# kr3.net
KiCad netlist of a schematic drawn in Altium Designer
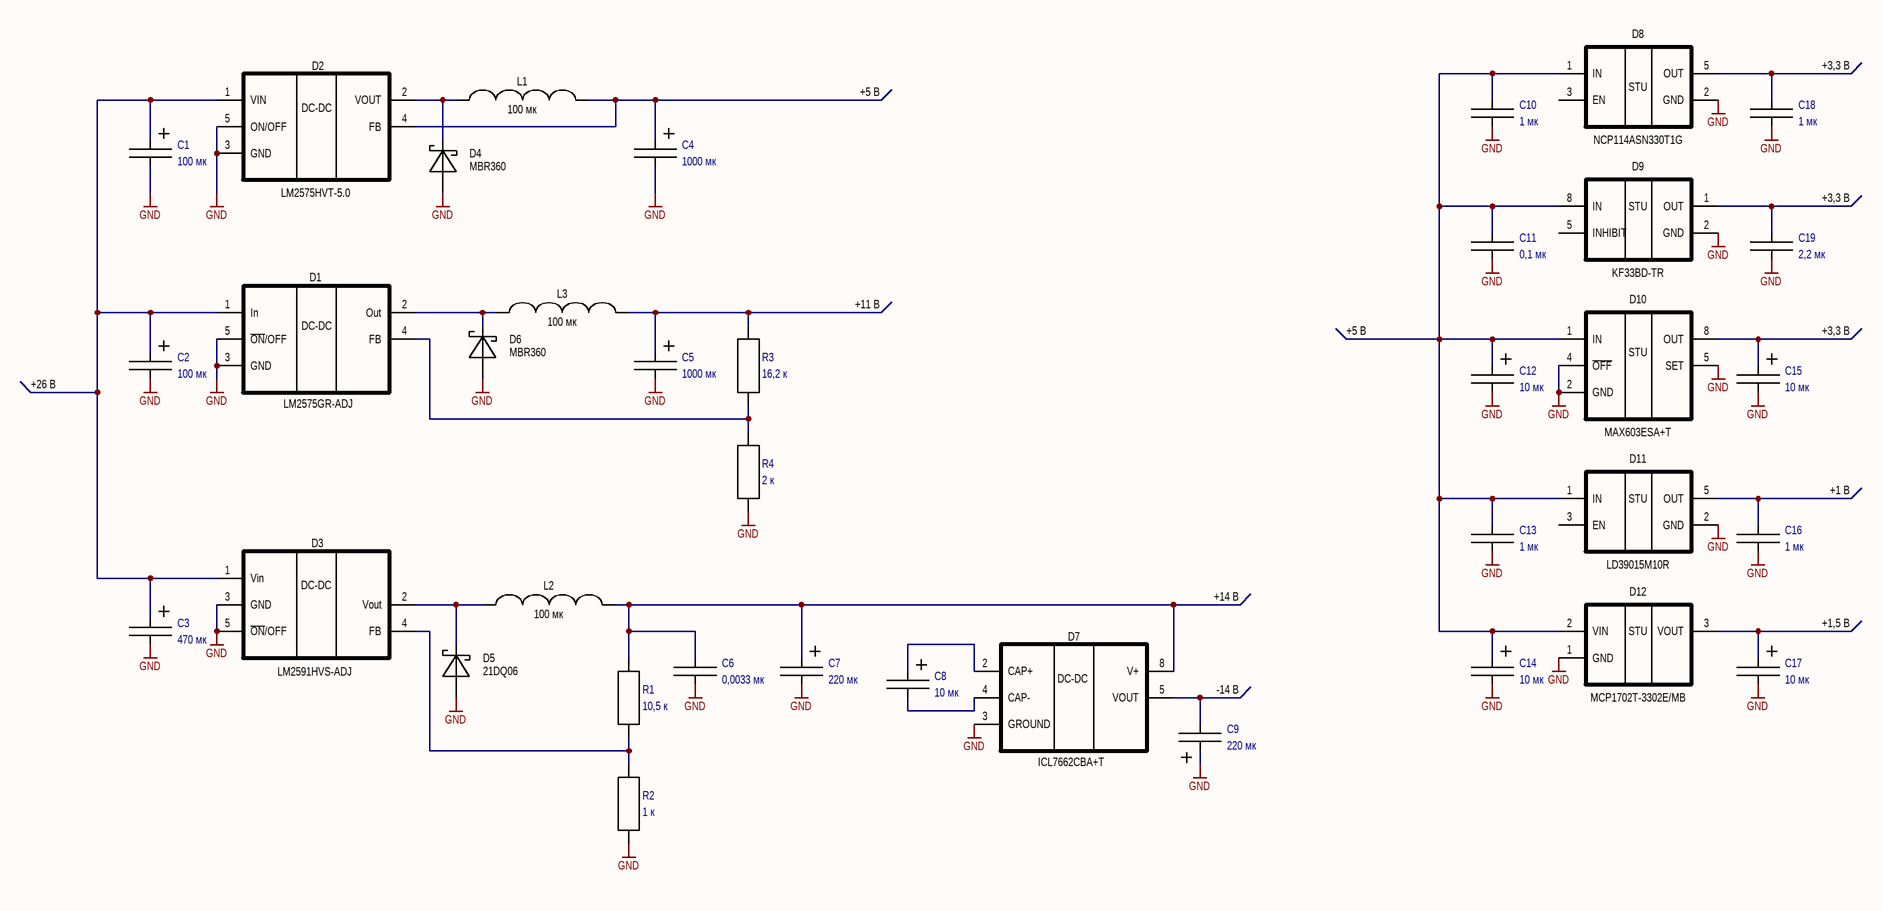
[diagram p0: kr3.SchDoc]

(export (version "E")
  (design (tool "Eeschema 10.0.6"))
  (components
    (comp (ref "C1")
      (value "100 мк")
      (fields (field (name "Comment") "100 мкФ ±* * * *, *"))
      (libsource (lib "STO") (part "C+"))
    )
    (comp (ref "C2")
      (value "100 мк")
      (fields (field (name "Comment") "100 мкФ ±* * * *, *"))
      (libsource (lib "STO") (part "C+"))
    )
    (comp (ref "C3")
      (value "470 мк")
      (fields (field (name "Comment") "470 мкФ ±* * * *, *"))
      (libsource (lib "STO") (part "C+"))
    )
    (comp (ref "C4")
      (value "1000 мк")
      (fields (field (name "Comment") "1000 мкФ ±* * * *, *"))
      (libsource (lib "STO") (part "C+"))
    )
    (comp (ref "C5")
      (value "1000 мк")
      (fields (field (name "Comment") "1000 мкФ ±* * * *, *"))
      (libsource (lib "STO") (part "C+"))
    )
    (comp (ref "C6")
      (value "0,0033 мк")
      (fields (field (name "Comment") "0,0033 мкФ ±* * * *, *"))
      (libsource (lib "STO") (part "C"))
    )
    (comp (ref "C7")
      (value "220 мк")
      (fields (field (name "Comment") "220 мкФ ±* * * *, *"))
      (libsource (lib "STO") (part "C+"))
    )
    (comp (ref "C8")
      (value "10 мк")
      (fields (field (name "Comment") "10 мкФ ±* * * *, *"))
      (libsource (lib "STO") (part "C+"))
    )
    (comp (ref "C9")
      (value "220 мк")
      (fields (field (name "Comment") "220 мкФ ±* * * *, *"))
      (libsource (lib "STO") (part "C+"))
    )
    (comp (ref "C10")
      (value "1 мк")
      (fields (field (name "Comment") "1 мкФ ±* * * *, *"))
      (libsource (lib "STO") (part "C"))
    )
    (comp (ref "C11")
      (value "0,1 мк")
      (fields (field (name "Comment") "0,1 мкФ ±* * * *, *"))
      (libsource (lib "STO") (part "C"))
    )
    (comp (ref "C12")
      (value "10 мк")
      (fields (field (name "Comment") "10 мкФ ±* * * *, *"))
      (libsource (lib "STO") (part "C+"))
    )
    (comp (ref "C13")
      (value "1 мк")
      (fields (field (name "Comment") "1 мкФ ±* * * *, *"))
      (libsource (lib "STO") (part "C"))
    )
    (comp (ref "C14")
      (value "10 мк")
      (fields (field (name "Comment") "10 мкФ ±* * * *, *"))
      (libsource (lib "STO") (part "C+"))
    )
    (comp (ref "C15")
      (value "10 мк")
      (fields (field (name "Comment") "10 мкФ ±* * * *, *"))
      (libsource (lib "STO") (part "C+"))
    )
    (comp (ref "C16")
      (value "1 мк")
      (fields (field (name "Comment") "1 мкФ ±* * * *, *"))
      (libsource (lib "STO") (part "C"))
    )
    (comp (ref "C17")
      (value "10 мк")
      (fields (field (name "Comment") "10 мкФ ±* * * *, *"))
      (libsource (lib "STO") (part "C+"))
    )
    (comp (ref "C18")
      (value "1 мк")
      (fields (field (name "Comment") "1 мкФ ±* * * *, *"))
      (libsource (lib "STO") (part "C"))
    )
    (comp (ref "C19")
      (value "2,2 мк")
      (fields (field (name "Comment") "2,2 мкФ ±* * * *, *"))
      (libsource (lib "STO") (part "C"))
    )
    (comp (ref "D1") (value "LM2575GR-ADJ") (libsource (lib "STO") (part "LM2575GR-ADJ")))
    (comp (ref "D2") (value "LM2575HVT-5.0") (libsource (lib "STO") (part "LM2575HVT-5.0")))
    (comp (ref "D3") (value "LM2591HVS-ADJ") (libsource (lib "STO") (part "LM2591HVS-ADJ")))
    (comp (ref "D4") (value "MBR360") (libsource (lib "STO") (part "MBR360")))
    (comp (ref "D5") (value "21DQ06") (libsource (lib "STO") (part "MBR360")))
    (comp (ref "D6") (value "MBR360") (libsource (lib "STO") (part "MBR360")))
    (comp (ref "D7") (value "ICL7662CBA+T") (libsource (lib "STO") (part "ICL7662CBA+T")))
    (comp (ref "D8") (value "NCP114ASN330T1G") (libsource (lib "STO") (part "NCP114ASN330T1G")))
    (comp (ref "D9") (value "KF33BD-TR") (libsource (lib "STO") (part "KF33BD-TR")))
    (comp (ref "D10") (value "MAX603ESA+T") (libsource (lib "STO") (part "MAX603ESA+T")))
    (comp (ref "D11") (value "LD39015M10R") (libsource (lib "STO") (part "LD39015M10R")))
    (comp (ref "D12") (value "MCP1702T-3302E/MB") (libsource (lib "STO") (part "MCP1702T-3302E/MB")))
    (comp (ref "L1") (value "100 мк") (libsource (lib "STO") (part "Inductor Sumida")))
    (comp (ref "L2") (value "100 мк") (libsource (lib "STO") (part "Inductor Sumida")))
    (comp (ref "L3") (value "100 мк") (libsource (lib "STO") (part "Inductor Sumida")))
    (comp (ref "R1")
      (value "10,5 к")
      (fields (field (name "Comment") "10,5 кОм ±* *, *"))
      (libsource (lib "STO") (part "R"))
    )
    (comp (ref "R2")
      (value "1 к")
      (fields (field (name "Comment") "1 кОм ±* *, *"))
      (libsource (lib "STO") (part "R"))
    )
    (comp (ref "R3")
      (value "16,2 к")
      (fields (field (name "Comment") "16,2 кОм ±* *, *"))
      (libsource (lib "STO") (part "R"))
    )
    (comp (ref "R4")
      (value "2 к")
      (fields (field (name "Comment") "2 кОм ±* *, *"))
      (libsource (lib "STO") (part "R"))
    )
  )
  (nets
    (net (code "1") (name "GND") (class "Default")
      (node (ref "C1") (pin "2") (pinfunction "2_2") (pintype "passive"))
      (node (ref "C10") (pin "2") (pinfunction "2_2") (pintype "passive"))
      (node (ref "C11") (pin "2") (pinfunction "2_2") (pintype "passive"))
      (node (ref "C12") (pin "2") (pinfunction "2_2") (pintype "passive"))
      (node (ref "C13") (pin "2") (pinfunction "2_2") (pintype "passive"))
      (node (ref "C14") (pin "2") (pinfunction "2_2") (pintype "passive"))
      (node (ref "C15") (pin "2") (pinfunction "2_2") (pintype "passive"))
      (node (ref "C16") (pin "2") (pinfunction "2_2") (pintype "passive"))
      (node (ref "C17") (pin "2") (pinfunction "2_2") (pintype "passive"))
      (node (ref "C18") (pin "2") (pinfunction "2_2") (pintype "passive"))
      (node (ref "C19") (pin "2") (pinfunction "2_2") (pintype "passive"))
      (node (ref "C2") (pin "2") (pinfunction "2_2") (pintype "passive"))
      (node (ref "C3") (pin "2") (pinfunction "2_2") (pintype "passive"))
      (node (ref "C4") (pin "2") (pinfunction "2_2") (pintype "passive"))
      (node (ref "C5") (pin "2") (pinfunction "2_2") (pintype "passive"))
      (node (ref "C6") (pin "2") (pinfunction "2_2") (pintype "passive"))
      (node (ref "C7") (pin "2") (pinfunction "2_2") (pintype "passive"))
      (node (ref "C9") (pin "1") (pinfunction "1_1") (pintype "passive"))
      (node (ref "D1") (pin "3") (pinfunction "GND_3") (pintype "passive"))
      (node (ref "D1") (pin "5") (pinfunction "~{ON}/OFF_5") (pintype "passive"))
      (node (ref "D10") (pin "2") (pinfunction "GND_2") (pintype "passive"))
      (node (ref "D10") (pin "4") (pinfunction "~{OFF}_4") (pintype "passive"))
      (node (ref "D10") (pin "5") (pinfunction "SET_5") (pintype "passive"))
      (node (ref "D11") (pin "2") (pinfunction "GND_2") (pintype "passive"))
      (node (ref "D12") (pin "1") (pinfunction "GND_1") (pintype "passive"))
      (node (ref "D2") (pin "3") (pinfunction "GND_3") (pintype "passive"))
      (node (ref "D2") (pin "5") (pinfunction "ON/OFF_5") (pintype "passive"))
      (node (ref "D3") (pin "3") (pinfunction "GND_3") (pintype "passive"))
      (node (ref "D3") (pin "5") (pinfunction "~{ON}/OFF_5") (pintype "passive"))
      (node (ref "D4") (pin "1") (pinfunction "A_1") (pintype "passive"))
      (node (ref "D5") (pin "1") (pinfunction "A_1") (pintype "passive"))
      (node (ref "D6") (pin "1") (pinfunction "A_1") (pintype "passive"))
      (node (ref "D7") (pin "3") (pinfunction "GROUND_3") (pintype "passive"))
      (node (ref "D8") (pin "2") (pinfunction "GND_2") (pintype "passive"))
      (node (ref "D9") (pin "2") (pinfunction "GND_2") (pintype "passive"))
      (node (ref "R2") (pin "2") (pinfunction "2_2") (pintype "passive"))
      (node (ref "R4") (pin "2") (pinfunction "2_2") (pintype "passive"))
    )
    (net (code "2") (name "Net-(C5-Pad1)") (class "Default")
      (node (ref "C5") (pin "1") (pinfunction "1_1") (pintype "passive"))
      (node (ref "R3") (pin "1") (pinfunction "1_1") (pintype "passive"))
    )
    (net (code "3") (name "Net-(D1-FB)") (class "Default")
      (node (ref "D1") (pin "4") (pinfunction "FB_4") (pintype "passive"))
      (node (ref "R3") (pin "2") (pinfunction "2_2") (pintype "passive"))
      (node (ref "R4") (pin "1") (pinfunction "1_1") (pintype "passive"))
    )
    (net (code "4") (name "Net-(D1-In)") (class "Default")
      (node (ref "C1") (pin "1") (pinfunction "1_1") (pintype "passive"))
      (node (ref "C2") (pin "1") (pinfunction "1_1") (pintype "passive"))
      (node (ref "C3") (pin "1") (pinfunction "1_1") (pintype "passive"))
      (node (ref "D1") (pin "1") (pinfunction "In_1") (pintype "passive"))
      (node (ref "D2") (pin "1") (pinfunction "VIN_1") (pintype "passive"))
      (node (ref "D3") (pin "1") (pinfunction "Vin_1") (pintype "passive"))
    )
    (net (code "5") (name "Net-(D1-Out)") (class "Default")
      (node (ref "D1") (pin "2") (pinfunction "Out_2") (pintype "passive"))
      (node (ref "D6") (pin "1") (pinfunction "C_1") (pintype "passive"))
    )
    (net (code "6") (name "Net-(D2-FB)") (class "Default")
      (node (ref "C4") (pin "1") (pinfunction "1_1") (pintype "passive"))
      (node (ref "D2") (pin "4") (pinfunction "FB_4") (pintype "passive"))
    )
    (net (code "7") (name "Net-(D2-VOUT)") (class "Default")
      (node (ref "D2") (pin "2") (pinfunction "VOUT_2") (pintype "passive"))
      (node (ref "D4") (pin "1") (pinfunction "C_1") (pintype "passive"))
    )
    (net (code "8") (name "Net-(D3-FB)") (class "Default")
      (node (ref "D3") (pin "4") (pinfunction "FB_4") (pintype "passive"))
      (node (ref "R1") (pin "2") (pinfunction "2_2") (pintype "passive"))
      (node (ref "R2") (pin "1") (pinfunction "1_1") (pintype "passive"))
    )
    (net (code "9") (name "Net-(D3-Vout)") (class "Default")
      (node (ref "D3") (pin "2") (pinfunction "Vout_2") (pintype "passive"))
      (node (ref "D5") (pin "1") (pinfunction "C_1") (pintype "passive"))
    )
    (net (code "10") (name "Net-(D7-CAP+)") (class "Default")
      (node (ref "C8") (pin "1") (pinfunction "1_1") (pintype "passive"))
      (node (ref "D7") (pin "2") (pinfunction "CAP+_2") (pintype "passive"))
    )
    (net (code "11") (name "Net-(D7-CAP-)") (class "Default")
      (node (ref "C8") (pin "2") (pinfunction "2_2") (pintype "passive"))
      (node (ref "D7") (pin "4") (pinfunction "CAP-_4") (pintype "passive"))
    )
    (net (code "12") (name "Net-(D7-V+)") (class "Default")
      (node (ref "C6") (pin "1") (pinfunction "1_1") (pintype "passive"))
      (node (ref "C7") (pin "1") (pinfunction "1_1") (pintype "passive"))
      (node (ref "D7") (pin "8") (pinfunction "V+_8") (pintype "passive"))
      (node (ref "R1") (pin "1") (pinfunction "1_1") (pintype "passive"))
    )
    (net (code "13") (name "Net-(D7-VOUT)") (class "Default")
      (node (ref "C9") (pin "2") (pinfunction "2_2") (pintype "passive"))
      (node (ref "D7") (pin "5") (pinfunction "VOUT_5") (pintype "passive"))
    )
    (net (code "14") (name "Net-(D8-OUT)") (class "Default")
      (node (ref "C18") (pin "1") (pinfunction "1_1") (pintype "passive"))
      (node (ref "D8") (pin "5") (pinfunction "OUT_5") (pintype "passive"))
    )
    (net (code "15") (name "Net-(D9-OUT)") (class "Default")
      (node (ref "C19") (pin "1") (pinfunction "1_1") (pintype "passive"))
      (node (ref "D9") (pin "1") (pinfunction "OUT_1") (pintype "passive"))
    )
    (net (code "16") (name "Net-(D10-IN)") (class "Default")
      (node (ref "C10") (pin "1") (pinfunction "1_1") (pintype "passive"))
      (node (ref "C11") (pin "1") (pinfunction "1_1") (pintype "passive"))
      (node (ref "C12") (pin "1") (pinfunction "1_1") (pintype "passive"))
      (node (ref "C13") (pin "1") (pinfunction "1_1") (pintype "passive"))
      (node (ref "C14") (pin "1") (pinfunction "1_1") (pintype "passive"))
      (node (ref "D10") (pin "1") (pinfunction "IN_1") (pintype "passive"))
      (node (ref "D11") (pin "1") (pinfunction "IN_1") (pintype "passive"))
      (node (ref "D12") (pin "2") (pinfunction "VIN_2") (pintype "passive"))
      (node (ref "D8") (pin "1") (pinfunction "IN_1") (pintype "passive"))
      (node (ref "D9") (pin "8") (pinfunction "IN_8") (pintype "passive"))
    )
    (net (code "17") (name "Net-(D10-OUT)") (class "Default")
      (node (ref "C15") (pin "1") (pinfunction "1_1") (pintype "passive"))
      (node (ref "D10") (pin "8") (pinfunction "OUT_8") (pintype "passive"))
    )
    (net (code "18") (name "Net-(D11-OUT)") (class "Default")
      (node (ref "C16") (pin "1") (pinfunction "1_1") (pintype "passive"))
      (node (ref "D11") (pin "5") (pinfunction "OUT_5") (pintype "passive"))
    )
    (net (code "19") (name "Net-(D12-VOUT)") (class "Default")
      (node (ref "C17") (pin "1") (pinfunction "1_1") (pintype "passive"))
      (node (ref "D12") (pin "3") (pinfunction "VOUT_3") (pintype "passive"))
    )
    (net (code "20") (name "unconnected-(D8-EN-Pad3)") (class "Default")
      (node (ref "D8") (pin "3") (pinfunction "EN_3") (pintype "passive"))
    )
    (net (code "21") (name "unconnected-(D9-INHIBIT-Pad5)") (class "Default")
      (node (ref "D9") (pin "5") (pinfunction "INHIBIT_5") (pintype "passive"))
    )
    (net (code "22") (name "unconnected-(D11-EN-Pad3)") (class "Default")
      (node (ref "D11") (pin "3") (pinfunction "EN_3") (pintype "passive"))
    )
  )
)
